# HFS_4011s_Rev_0.net
KiCad netlist of a schematic drawn in EAGLE
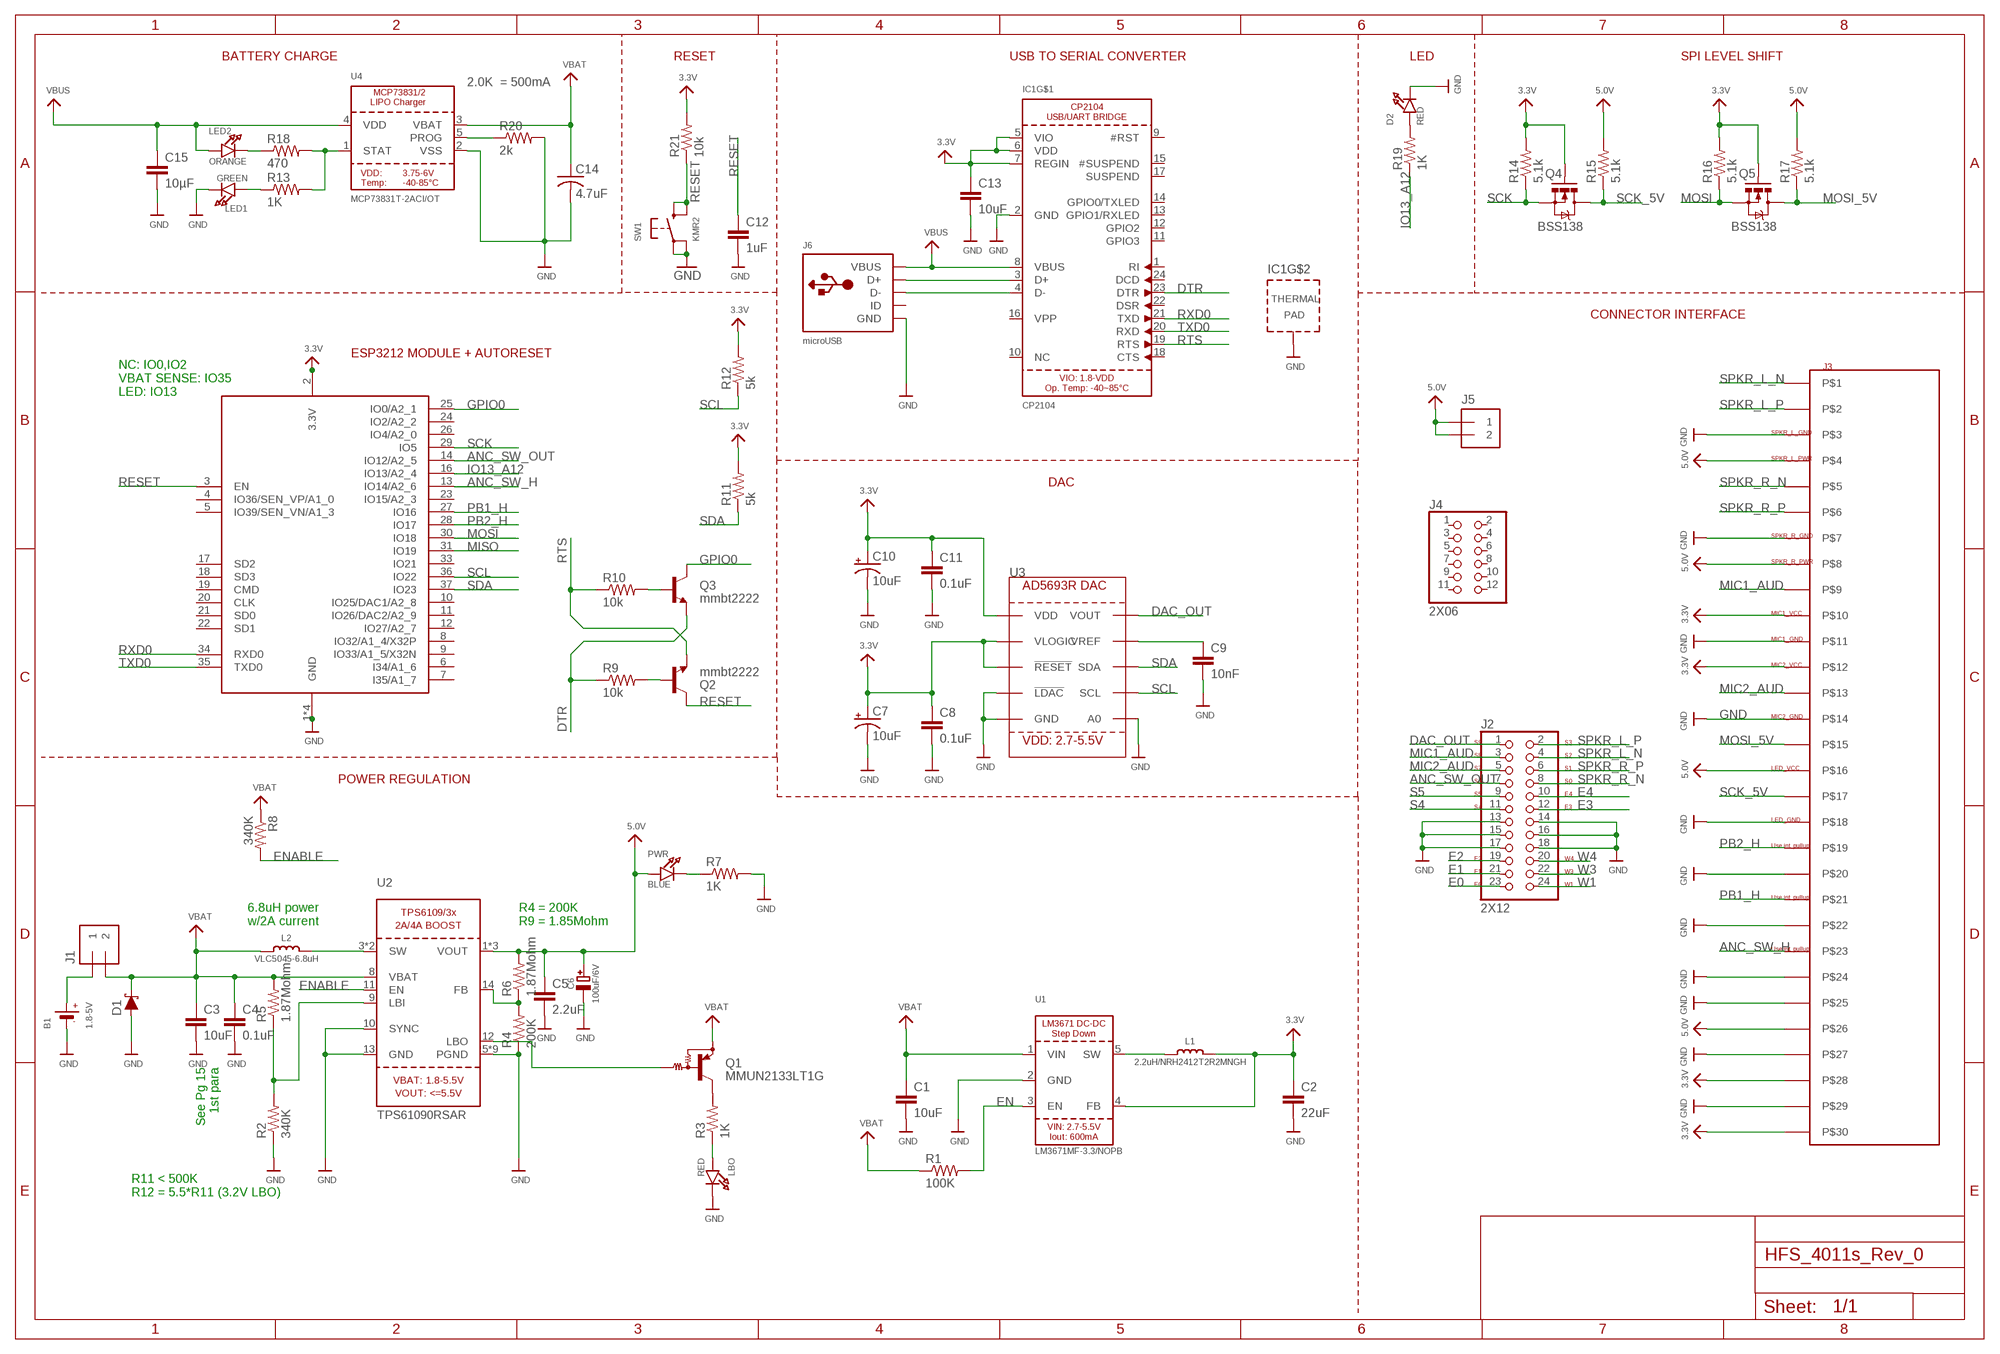
[diagram p0: schematic, sheet 1]

(export (version "E")
  (design (tool "Eeschema 10.0.6"))
  (components
    (comp (ref "B1")
      (value "1.8-5V")
      (footprint "eagle-import:JSTPH2")
      (libsource (lib "eagle-import") (part "BATTERY"))
    )
    (comp (ref "C1")
      (value "10uF")
      (footprint "eagle-import:C0603")
      (libsource (lib "eagle-import") (part "C-EUC0603"))
    )
    (comp (ref "C2")
      (value "22uF")
      (footprint "eagle-import:C0603")
      (libsource (lib "eagle-import") (part "C-EUC0603"))
    )
    (comp (ref "C3")
      (value "10uF")
      (footprint "eagle-import:C0603")
      (libsource (lib "eagle-import") (part "C-EUC0603"))
    )
    (comp (ref "C4")
      (value "0.1uF")
      (footprint "eagle-import:C0603")
      (libsource (lib "eagle-import") (part "C-EUC0603"))
    )
    (comp (ref "C5")
      (value "2.2uF")
      (footprint "eagle-import:C0603")
      (libsource (lib "eagle-import") (part "C-EUC0603"))
    )
    (comp (ref "C6")
      (value "100uF/6V")
      (footprint "eagle-import:EIA3528-21_B-R")
      (libsource (lib "eagle-import") (part "CAP_TANTALUMB/3528_REFLOW"))
    )
    (comp (ref "C7")
      (value "10uF")
      (footprint "eagle-import:EIA3216")
      (libsource (lib "eagle-import") (part "10UF-TANT"))
    )
    (comp (ref "C8")
      (value "0.1uF")
      (footprint "eagle-import:C0603")
      (libsource (lib "eagle-import") (part "C-EUC0603"))
    )
    (comp (ref "C9")
      (value "10nF")
      (footprint "eagle-import:C0603")
      (libsource (lib "eagle-import") (part "C-EUC0603"))
    )
    (comp (ref "C10")
      (value "10uF")
      (footprint "eagle-import:EIA3216")
      (libsource (lib "eagle-import") (part "10UF-TANT"))
    )
    (comp (ref "C11")
      (value "0.1uF")
      (footprint "eagle-import:C0603")
      (libsource (lib "eagle-import") (part "C-EUC0603"))
    )
    (comp (ref "C12")
      (value "1uF")
      (footprint "eagle-import:C0603")
      (libsource (lib "eagle-import") (part "C-EUC0603"))
    )
    (comp (ref "C13")
      (value "10uF")
      (footprint "eagle-import:C0603")
      (libsource (lib "eagle-import") (part "C-EUC0603"))
    )
    (comp (ref "C14")
      (value "4.7uF")
      (footprint "eagle-import:C1206")
      (libsource (lib "eagle-import") (part "C-USC1206"))
    )
    (comp (ref "C15")
      (value "10µF")
      (footprint "eagle-import:C0603")
      (libsource (lib "eagle-import") (part "C-EUC0603"))
    )
    (comp (ref "D1")
      (value "SMAJ5.0CALFDKR-ND")
      (footprint "eagle-import:DO-214AC")
      (libsource (lib "eagle-import") (part "SMAJ5.0CALFDKR-ND"))
    )
    (comp (ref "D2")
      (value "RED")
      (footprint "eagle-import:CHIPLED_0805_NOOUTLINE")
      (libsource (lib "eagle-import") (part "LED0805_NOOUTLINE"))
    )
    (comp (ref "IC1")
      (value "CP2104")
      (footprint "eagle-import:QFN24_4MM_SMSC")
      (libsource (lib "eagle-import") (part "CP2104"))
    )
    (comp (ref "J1")
      (value "1X02")
      (footprint "eagle-import:1X02")
      (libsource (lib "eagle-import") (part "1X02"))
    )
    (comp (ref "J2")
      (value "2X12")
      (footprint "eagle-import:2X12")
      (libsource (lib "eagle-import") (part "2X12"))
    )
    (comp (ref "J3")
      (value "MOLEX_IGRID_15X2CONNECTOR")
      (footprint "eagle-import:MOLEX_IGRID15X2CONNECTOR")
      (libsource (lib "eagle-import") (part "MOLEX_IGRID_15X2CONNECTOR"))
    )
    (comp (ref "J4")
      (value "2X06")
      (footprint "eagle-import:2X06")
      (libsource (lib "eagle-import") (part "2X06"))
    )
    (comp (ref "J5")
      (value "1X02")
      (footprint "eagle-import:1X02")
      (libsource (lib "eagle-import") (part "1X02"))
    )
    (comp (ref "J6")
      (value "microUSB")
      (footprint "eagle-import:4UCONN_20329")
      (libsource (lib "eagle-import") (part "USBMICRO_20329"))
    )
    (comp (ref "L1")
      (value "2.2uH/NRH2412T2R2MNGH")
      (footprint "eagle-import:INDUCTOR_TAIYOYUDEN_NRH2412T")
      (libsource (lib "eagle-import") (part "INDUCTORNRH2412T"))
    )
    (comp (ref "L2")
      (value "VLC5045-6.8uH")
      (footprint "eagle-import:INDUCTOR_5X5MM_TDK_VLC5045")
      (libsource (lib "eagle-import") (part "INDUCTORTDK_VLC5045"))
    )
    (comp (ref "LBO")
      (value "RED")
      (footprint "eagle-import:CHIPLED_0805_NOOUTLINE")
      (libsource (lib "eagle-import") (part "LED0805_NOOUTLINE"))
    )
    (comp (ref "LED1")
      (value "GREEN")
      (footprint "eagle-import:CHIPLED_0805_NOOUTLINE")
      (libsource (lib "eagle-import") (part "LED0805_NOOUTLINE"))
    )
    (comp (ref "LED2")
      (value "ORANGE")
      (footprint "eagle-import:CHIPLED_0805_NOOUTLINE")
      (libsource (lib "eagle-import") (part "LED0805_NOOUTLINE"))
    )
    (comp (ref "PWR")
      (value "BLUE")
      (footprint "eagle-import:CHIPLED_0805_NOOUTLINE")
      (libsource (lib "eagle-import") (part "LED0805_NOOUTLINE"))
    )
    (comp (ref "Q1")
      (value "MMUN2133LT1G")
      (footprint "eagle-import:SC59-BEC")
      (libsource (lib "eagle-import") (part "-PNP_DRIVER-SC59-BECMUN2114T1"))
    )
    (comp (ref "Q2")
      (value "mmbt2222")
      (footprint "eagle-import:SOT23-3")
      (libsource (lib "eagle-import") (part "TRANSISTOR_NPNSOT23-3"))
    )
    (comp (ref "Q3")
      (value "mmbt2222")
      (footprint "eagle-import:SOT23-3")
      (libsource (lib "eagle-import") (part "TRANSISTOR_NPNSOT23-3"))
    )
    (comp (ref "Q4")
      (value "BSS138")
      (footprint "eagle-import:SOT23-3")
      (libsource (lib "eagle-import") (part "MOSFET-NCHANNELSMD"))
    )
    (comp (ref "Q5")
      (value "BSS138")
      (footprint "eagle-import:SOT23-3")
      (libsource (lib "eagle-import") (part "MOSFET-NCHANNELSMD"))
    )
    (comp (ref "R1")
      (value "100K")
      (footprint "eagle-import:R0603")
      (libsource (lib "eagle-import") (part "R-US_R0603"))
    )
    (comp (ref "R2")
      (value "340K")
      (footprint "eagle-import:R0603")
      (libsource (lib "eagle-import") (part "R-US_R0603"))
    )
    (comp (ref "R3")
      (value "1K")
      (footprint "eagle-import:R0603")
      (libsource (lib "eagle-import") (part "R-US_R0603"))
    )
    (comp (ref "R4")
      (value "200K")
      (footprint "eagle-import:R0603")
      (libsource (lib "eagle-import") (part "R-US_R0603"))
    )
    (comp (ref "R5")
      (value "1.87Mohm")
      (footprint "eagle-import:R0603")
      (libsource (lib "eagle-import") (part "R-US_R0603"))
    )
    (comp (ref "R6")
      (value "1.87Mohm")
      (footprint "eagle-import:R0603")
      (libsource (lib "eagle-import") (part "R-US_R0603"))
    )
    (comp (ref "R7")
      (value "1K")
      (footprint "eagle-import:R0603")
      (libsource (lib "eagle-import") (part "R-US_R0603"))
    )
    (comp (ref "R8")
      (value "340K")
      (footprint "eagle-import:R0603")
      (libsource (lib "eagle-import") (part "R-US_R0603"))
    )
    (comp (ref "R9")
      (value "10k")
      (footprint "eagle-import:R0603")
      (libsource (lib "eagle-import") (part "R-US_R0603"))
    )
    (comp (ref "R10")
      (value "10k")
      (footprint "eagle-import:R0603")
      (libsource (lib "eagle-import") (part "R-US_R0603"))
    )
    (comp (ref "R11")
      (value "5k")
      (footprint "eagle-import:R0603")
      (libsource (lib "eagle-import") (part "R-US_R0603"))
    )
    (comp (ref "R12")
      (value "5k")
      (footprint "eagle-import:R0603")
      (libsource (lib "eagle-import") (part "R-US_R0603"))
    )
    (comp (ref "R13")
      (value "1K")
      (footprint "eagle-import:R0603")
      (libsource (lib "eagle-import") (part "R-US_R0603"))
    )
    (comp (ref "R14")
      (value "5.1k")
      (footprint "eagle-import:R0603")
      (libsource (lib "eagle-import") (part "R-US_R0603"))
    )
    (comp (ref "R15")
      (value "5.1k")
      (footprint "eagle-import:R0603")
      (libsource (lib "eagle-import") (part "R-US_R0603"))
    )
    (comp (ref "R16")
      (value "5.1k")
      (footprint "eagle-import:R0603")
      (libsource (lib "eagle-import") (part "R-US_R0603"))
    )
    (comp (ref "R17")
      (value "5.1k")
      (footprint "eagle-import:R0603")
      (libsource (lib "eagle-import") (part "R-US_R0603"))
    )
    (comp (ref "R18")
      (value "470")
      (footprint "eagle-import:R0603")
      (libsource (lib "eagle-import") (part "R-US_R0603"))
    )
    (comp (ref "R19")
      (value "1K")
      (footprint "eagle-import:R0603")
      (libsource (lib "eagle-import") (part "R-US_R0603"))
    )
    (comp (ref "R20")
      (value "2k")
      (footprint "eagle-import:R0603")
      (libsource (lib "eagle-import") (part "R-US_R0603"))
    )
    (comp (ref "R21")
      (value "10k")
      (footprint "eagle-import:R0603")
      (libsource (lib "eagle-import") (part "R-US_R0603"))
    )
    (comp (ref "SW1")
      (value "KMR2")
      (footprint "eagle-import:BTN_KMR2_4.6X2.8")
      (libsource (lib "eagle-import") (part "SWITCH_TACT_SMT4.6X2.8"))
    )
    (comp (ref "U1")
      (value "LM3671MF-3.3/NOPB")
      (footprint "eagle-import:SOT23-5")
      (libsource (lib "eagle-import") (part "VREG_LM3671"))
    )
    (comp (ref "U2")
      (value "TPS61090RSAR")
      (footprint "eagle-import:PVQFN-16")
      (libsource (lib "eagle-import") (part "VREG_TPS6103X"))
    )
    (comp (ref "U3")
      (value "AD5693R")
      (footprint "eagle-import:MSOP10")
      (libsource (lib "eagle-import") (part "AD5693R"))
    )
    (comp (ref "U4")
      (value "MCP73831T-2ACI/OT")
      (footprint "eagle-import:SOT23-5")
      (libsource (lib "eagle-import") (part "MCP73831/2"))
    )
    (comp (ref "X1")
      (value "ESP32_WROOM32_SKINNY")
      (footprint "eagle-import:WROOM32_SKINNY")
      (libsource (lib "eagle-import") (part "ESP32_WROOM32_SKINNY"))
    )
  )
  (nets
    (net (code "1") (name "/ANC_SW_H") (class "Default")
      (node (ref "J3") (pin "P$23") (pinfunction "P$23_P$23") (pintype "bidirectional"))
      (node (ref "X1") (pin "13") (pinfunction "IO14/A2_6_13") (pintype "bidirectional"))
    )
    (net (code "2") (name "/ANC_SW_OUT") (class "Default")
      (node (ref "J2") (pin "7") (pinfunction "7_7") (pintype "passive"))
      (node (ref "X1") (pin "14") (pinfunction "IO12/A2_5_14") (pintype "bidirectional"))
    )
    (net (code "3") (name "/DAC_OUT") (class "Default")
      (node (ref "J2") (pin "1") (pinfunction "1_1") (pintype "passive"))
      (node (ref "U3") (pin "10") (pinfunction "VOUT_10") (pintype "passive"))
    )
    (net (code "4") (name "/DTR") (class "Default")
      (node (ref "IC1") (pin "23") (pinfunction "DTR_23") (pintype "output"))
      (node (ref "Q3") (pin "2") (pinfunction "E_2") (pintype "passive"))
      (node (ref "R9") (pin "1") (pinfunction "1_1") (pintype "passive"))
    )
    (net (code "5") (name "/E0") (class "Default")
      (node (ref "J2") (pin "23") (pinfunction "23_23") (pintype "passive"))
    )
    (net (code "6") (name "/E1") (class "Default")
      (node (ref "J2") (pin "21") (pinfunction "21_21") (pintype "passive"))
    )
    (net (code "7") (name "/E2") (class "Default")
      (node (ref "J2") (pin "19") (pinfunction "19_19") (pintype "passive"))
    )
    (net (code "8") (name "/E3") (class "Default")
      (node (ref "J2") (pin "12") (pinfunction "12_12") (pintype "passive"))
    )
    (net (code "9") (name "/E4") (class "Default")
      (node (ref "J2") (pin "10") (pinfunction "10_10") (pintype "passive"))
    )
    (net (code "10") (name "/EN") (class "Default")
      (node (ref "R1") (pin "2") (pinfunction "2_2") (pintype "passive"))
      (node (ref "U1") (pin "3") (pinfunction "EN_3") (pintype "input"))
    )
    (net (code "11") (name "/ENABLE") (class "Default")
      (node (ref "R8") (pin "2") (pinfunction "2_2") (pintype "passive"))
      (node (ref "U2") (pin "11") (pinfunction "EN_11") (pintype "input"))
    )
    (net (code "12") (name "/GPIO0") (class "Default")
      (node (ref "Q3") (pin "3") (pinfunction "C_3") (pintype "passive"))
      (node (ref "X1") (pin "25") (pinfunction "IO0/A2_1_25") (pintype "bidirectional"))
    )
    (net (code "13") (name "/IO13_A12") (class "Default")
      (node (ref "R19") (pin "1") (pinfunction "1_1") (pintype "passive"))
      (node (ref "X1") (pin "16") (pinfunction "IO13/A2_4_16") (pintype "bidirectional"))
    )
    (net (code "14") (name "/MIC1_AUD") (class "Default")
      (node (ref "J2") (pin "3") (pinfunction "3_3") (pintype "passive"))
      (node (ref "J3") (pin "P$9") (pinfunction "P$9_P$9") (pintype "bidirectional"))
    )
    (net (code "15") (name "/MIC2_AUD") (class "Default")
      (node (ref "J2") (pin "5") (pinfunction "5_5") (pintype "passive"))
      (node (ref "J3") (pin "P$13") (pinfunction "P$13_P$13") (pintype "bidirectional"))
    )
    (net (code "16") (name "/MISO") (class "Default")
      (node (ref "X1") (pin "31") (pinfunction "IO19_31") (pintype "bidirectional"))
    )
    (net (code "17") (name "/MOSI") (class "Default")
      (node (ref "Q5") (pin "2") (pinfunction "S_2") (pintype "passive"))
      (node (ref "R16") (pin "1") (pinfunction "1_1") (pintype "passive"))
      (node (ref "X1") (pin "30") (pinfunction "IO18_30") (pintype "bidirectional"))
    )
    (net (code "18") (name "/MOSI_5V") (class "Default")
      (node (ref "J3") (pin "P$15") (pinfunction "P$15_P$15") (pintype "bidirectional"))
      (node (ref "Q5") (pin "3") (pinfunction "D_3") (pintype "passive"))
      (node (ref "R17") (pin "1") (pinfunction "1_1") (pintype "passive"))
    )
    (net (code "19") (name "/PB1_H") (class "Default")
      (node (ref "J3") (pin "P$21") (pinfunction "P$21_P$21") (pintype "bidirectional"))
      (node (ref "X1") (pin "27") (pinfunction "IO16_27") (pintype "bidirectional"))
    )
    (net (code "20") (name "/PB2_H") (class "Default")
      (node (ref "J3") (pin "P$19") (pinfunction "P$19_P$19") (pintype "bidirectional"))
      (node (ref "X1") (pin "28") (pinfunction "IO17_28") (pintype "bidirectional"))
    )
    (net (code "21") (name "/RESET") (class "Default")
      (node (ref "C12") (pin "1") (pinfunction "1_1") (pintype "passive"))
      (node (ref "Q2") (pin "3") (pinfunction "C_3") (pintype "passive"))
      (node (ref "R21") (pin "1") (pinfunction "1_1") (pintype "passive"))
      (node (ref "SW1") (pin "B") (pinfunction "S_B") (pintype "passive"))
      (node (ref "SW1") (pin "B'") (pinfunction "S1_B'") (pintype "passive"))
      (node (ref "X1") (pin "3") (pinfunction "EN_3") (pintype "input"))
    )
    (net (code "22") (name "/RTS") (class "Default")
      (node (ref "IC1") (pin "19") (pinfunction "RTS_19") (pintype "output"))
      (node (ref "Q2") (pin "2") (pinfunction "E_2") (pintype "passive"))
      (node (ref "R10") (pin "1") (pinfunction "1_1") (pintype "passive"))
    )
    (net (code "23") (name "/RXD0") (class "Default")
      (node (ref "IC1") (pin "21") (pinfunction "TXD_21") (pintype "output"))
      (node (ref "X1") (pin "34") (pinfunction "RXD0_34") (pintype "input"))
    )
    (net (code "24") (name "/S4") (class "Default")
      (node (ref "J2") (pin "11") (pinfunction "11_11") (pintype "passive"))
    )
    (net (code "25") (name "/S5") (class "Default")
      (node (ref "J2") (pin "9") (pinfunction "9_9") (pintype "passive"))
    )
    (net (code "26") (name "/SCK") (class "Default")
      (node (ref "Q4") (pin "2") (pinfunction "S_2") (pintype "passive"))
      (node (ref "R14") (pin "1") (pinfunction "1_1") (pintype "passive"))
      (node (ref "X1") (pin "29") (pinfunction "IO5_29") (pintype "bidirectional"))
    )
    (net (code "27") (name "/SCK_5V") (class "Default")
      (node (ref "J3") (pin "P$17") (pinfunction "P$17_P$17") (pintype "bidirectional"))
      (node (ref "Q4") (pin "3") (pinfunction "D_3") (pintype "passive"))
      (node (ref "R15") (pin "1") (pinfunction "1_1") (pintype "passive"))
    )
    (net (code "28") (name "/SCL") (class "Default")
      (node (ref "R12") (pin "1") (pinfunction "1_1") (pintype "passive"))
      (node (ref "U3") (pin "7") (pinfunction "SCL_7") (pintype "passive"))
      (node (ref "X1") (pin "36") (pinfunction "IO22_36") (pintype "bidirectional"))
    )
    (net (code "29") (name "/SDA") (class "Default")
      (node (ref "R11") (pin "1") (pinfunction "1_1") (pintype "passive"))
      (node (ref "U3") (pin "8") (pinfunction "SDA_8") (pintype "passive"))
      (node (ref "X1") (pin "37") (pinfunction "IO23_37") (pintype "bidirectional"))
    )
    (net (code "30") (name "/SPKR_L_N") (class "Default")
      (node (ref "J2") (pin "4") (pinfunction "4_4") (pintype "passive"))
      (node (ref "J3") (pin "P$1") (pinfunction "P$1_P$1") (pintype "bidirectional"))
    )
    (net (code "31") (name "/SPKR_L_P") (class "Default")
      (node (ref "J2") (pin "2") (pinfunction "2_2") (pintype "passive"))
      (node (ref "J3") (pin "P$2") (pinfunction "P$2_P$2") (pintype "bidirectional"))
    )
    (net (code "32") (name "/SPKR_R_N") (class "Default")
      (node (ref "J2") (pin "8") (pinfunction "8_8") (pintype "passive"))
      (node (ref "J3") (pin "P$5") (pinfunction "P$5_P$5") (pintype "bidirectional"))
    )
    (net (code "33") (name "/SPKR_R_P") (class "Default")
      (node (ref "J2") (pin "6") (pinfunction "6_6") (pintype "passive"))
      (node (ref "J3") (pin "P$6") (pinfunction "P$6_P$6") (pintype "bidirectional"))
    )
    (net (code "34") (name "/TXD0") (class "Default")
      (node (ref "IC1") (pin "20") (pinfunction "RXD_20") (pintype "input"))
      (node (ref "X1") (pin "35") (pinfunction "TXD0_35") (pintype "output"))
    )
    (net (code "35") (name "/W1") (class "Default")
      (node (ref "J2") (pin "24") (pinfunction "24_24") (pintype "passive"))
    )
    (net (code "36") (name "/W3") (class "Default")
      (node (ref "J2") (pin "22") (pinfunction "22_22") (pintype "passive"))
    )
    (net (code "37") (name "/W4") (class "Default")
      (node (ref "J2") (pin "20") (pinfunction "20_20") (pintype "passive"))
    )
    (net (code "38") (name "3.3V") (class "Default")
      (node (ref "C10") (pin "A") (pinfunction "+_A") (pintype "passive"))
      (node (ref "C11") (pin "1") (pinfunction "1_1") (pintype "passive"))
      (node (ref "C13") (pin "1") (pinfunction "1_1") (pintype "passive"))
      (node (ref "C2") (pin "1") (pinfunction "1_1") (pintype "passive"))
      (node (ref "C7") (pin "A") (pinfunction "+_A") (pintype "passive"))
      (node (ref "C8") (pin "1") (pinfunction "1_1") (pintype "passive"))
      (node (ref "IC1") (pin "5") (pinfunction "VIO_5") (pintype "power_in"))
      (node (ref "IC1") (pin "6") (pinfunction "VDD_6") (pintype "power_in"))
      (node (ref "IC1") (pin "7") (pinfunction "REGIN_7") (pintype "power_in"))
      (node (ref "J3") (pin "P$10") (pinfunction "P$10_P$10") (pintype "bidirectional"))
      (node (ref "J3") (pin "P$12") (pinfunction "P$12_P$12") (pintype "bidirectional"))
      (node (ref "J3") (pin "P$28") (pinfunction "P$28_P$28") (pintype "bidirectional"))
      (node (ref "J3") (pin "P$30") (pinfunction "P$30_P$30") (pintype "bidirectional"))
      (node (ref "L1") (pin "2") (pinfunction "2_2") (pintype "passive"))
      (node (ref "Q4") (pin "1") (pinfunction "G_1") (pintype "passive"))
      (node (ref "Q5") (pin "1") (pinfunction "G_1") (pintype "passive"))
      (node (ref "R11") (pin "2") (pinfunction "2_2") (pintype "passive"))
      (node (ref "R12") (pin "2") (pinfunction "2_2") (pintype "passive"))
      (node (ref "R14") (pin "2") (pinfunction "2_2") (pintype "passive"))
      (node (ref "R16") (pin "2") (pinfunction "2_2") (pintype "passive"))
      (node (ref "R21") (pin "2") (pinfunction "2_2") (pintype "passive"))
      (node (ref "U1") (pin "4") (pinfunction "FB_4") (pintype "power_in"))
      (node (ref "U3") (pin "1") (pinfunction "VDD_1") (pintype "passive"))
      (node (ref "U3") (pin "2") (pinfunction "VLOGIC_2") (pintype "passive"))
      (node (ref "U3") (pin "3") (pinfunction "~{RESET}_3") (pintype "passive"))
      (node (ref "X1") (pin "2") (pinfunction "3.3V_2") (pintype "passive"))
    )
    (net (code "39") (name "5.0V") (class "Default")
      (node (ref "C5") (pin "1") (pinfunction "1_1") (pintype "passive"))
      (node (ref "C6") (pin "+") (pinfunction "+_+") (pintype "passive"))
      (node (ref "J3") (pin "P$16") (pinfunction "P$16_P$16") (pintype "bidirectional"))
      (node (ref "J3") (pin "P$26") (pinfunction "P$26_P$26") (pintype "bidirectional"))
      (node (ref "J3") (pin "P$4") (pinfunction "P$4_P$4") (pintype "bidirectional"))
      (node (ref "J3") (pin "P$8") (pinfunction "P$8_P$8") (pintype "bidirectional"))
      (node (ref "J5") (pin "1") (pinfunction "1_1") (pintype "passive"))
      (node (ref "J5") (pin "2") (pinfunction "2_2") (pintype "passive"))
      (node (ref "PWR") (pin "A") (pinfunction "A_A") (pintype "passive"))
      (node (ref "R15") (pin "2") (pinfunction "2_2") (pintype "passive"))
      (node (ref "R17") (pin "2") (pinfunction "2_2") (pintype "passive"))
      (node (ref "R6") (pin "2") (pinfunction "2_2") (pintype "passive"))
      (node (ref "U2") (pin "1") (pinfunction "VOUT_1") (pintype "power_in"))
      (node (ref "U2") (pin "15") (pinfunction "VOUT_15") (pintype "power_in"))
      (node (ref "U2") (pin "16") (pinfunction "VOUT_16") (pintype "power_in"))
    )
    (net (code "40") (name "GND") (class "Default")
      (node (ref "B1") (pin "1") (pinfunction "-_1") (pintype "passive"))
      (node (ref "C1") (pin "2") (pinfunction "2_2") (pintype "passive"))
      (node (ref "C10") (pin "C") (pinfunction "-_C") (pintype "passive"))
      (node (ref "C11") (pin "2") (pinfunction "2_2") (pintype "passive"))
      (node (ref "C12") (pin "2") (pinfunction "2_2") (pintype "passive"))
      (node (ref "C13") (pin "2") (pinfunction "2_2") (pintype "passive"))
      (node (ref "C14") (pin "2") (pinfunction "2_2") (pintype "passive"))
      (node (ref "C15") (pin "2") (pinfunction "2_2") (pintype "passive"))
      (node (ref "C2") (pin "2") (pinfunction "2_2") (pintype "passive"))
      (node (ref "C3") (pin "2") (pinfunction "2_2") (pintype "passive"))
      (node (ref "C4") (pin "2") (pinfunction "2_2") (pintype "passive"))
      (node (ref "C5") (pin "2") (pinfunction "2_2") (pintype "passive"))
      (node (ref "C6") (pin "-") (pinfunction "-_-") (pintype "passive"))
      (node (ref "C7") (pin "C") (pinfunction "-_C") (pintype "passive"))
      (node (ref "C8") (pin "2") (pinfunction "2_2") (pintype "passive"))
      (node (ref "C9") (pin "2") (pinfunction "2_2") (pintype "passive"))
      (node (ref "D1") (pin "A") (pinfunction "A_A") (pintype "passive"))
      (node (ref "D2") (pin "C") (pinfunction "C_C") (pintype "passive"))
      (node (ref "IC1") (pin "2") (pinfunction "GND_2") (pintype "power_in"))
      (node (ref "IC1") (pin "THERM") (pinfunction "TP_THERM") (pintype "power_in"))
      (node (ref "J2") (pin "13") (pinfunction "13_13") (pintype "passive"))
      (node (ref "J2") (pin "14") (pinfunction "14_14") (pintype "passive"))
      (node (ref "J2") (pin "15") (pinfunction "15_15") (pintype "passive"))
      (node (ref "J2") (pin "16") (pinfunction "16_16") (pintype "passive"))
      (node (ref "J2") (pin "17") (pinfunction "17_17") (pintype "passive"))
      (node (ref "J2") (pin "18") (pinfunction "18_18") (pintype "passive"))
      (node (ref "J3") (pin "P$11") (pinfunction "P$11_P$11") (pintype "bidirectional"))
      (node (ref "J3") (pin "P$14") (pinfunction "P$14_P$14") (pintype "bidirectional"))
      (node (ref "J3") (pin "P$18") (pinfunction "P$18_P$18") (pintype "bidirectional"))
      (node (ref "J3") (pin "P$20") (pinfunction "P$20_P$20") (pintype "bidirectional"))
      (node (ref "J3") (pin "P$22") (pinfunction "P$22_P$22") (pintype "bidirectional"))
      (node (ref "J3") (pin "P$24") (pinfunction "P$24_P$24") (pintype "bidirectional"))
      (node (ref "J3") (pin "P$25") (pinfunction "P$25_P$25") (pintype "bidirectional"))
      (node (ref "J3") (pin "P$27") (pinfunction "P$27_P$27") (pintype "bidirectional"))
      (node (ref "J3") (pin "P$29") (pinfunction "P$29_P$29") (pintype "bidirectional"))
      (node (ref "J3") (pin "P$3") (pinfunction "P$3_P$3") (pintype "bidirectional"))
      (node (ref "J3") (pin "P$7") (pinfunction "P$7_P$7") (pintype "bidirectional"))
      (node (ref "J6") (pin "BASE@1") (pinfunction "GND_BASE@1") (pintype "power_in"))
      (node (ref "J6") (pin "BASE@2") (pinfunction "GND_BASE@2") (pintype "power_in"))
      (node (ref "J6") (pin "GND") (pinfunction "GND_GND") (pintype "power_in"))
      (node (ref "J6") (pin "SPRT@1") (pinfunction "GND_SPRT@1") (pintype "power_in"))
      (node (ref "J6") (pin "SPRT@2") (pinfunction "GND_SPRT@2") (pintype "power_in"))
      (node (ref "J6") (pin "SPRT@3") (pinfunction "GND_SPRT@3") (pintype "power_in"))
      (node (ref "J6") (pin "SPRT@4") (pinfunction "GND_SPRT@4") (pintype "power_in"))
      (node (ref "LBO") (pin "C") (pinfunction "C_C") (pintype "passive"))
      (node (ref "LED1") (pin "C") (pinfunction "C_C") (pintype "passive"))
      (node (ref "R2") (pin "1") (pinfunction "1_1") (pintype "passive"))
      (node (ref "R20") (pin "2") (pinfunction "2_2") (pintype "passive"))
      (node (ref "R4") (pin "1") (pinfunction "1_1") (pintype "passive"))
      (node (ref "R7") (pin "2") (pinfunction "2_2") (pintype "passive"))
      (node (ref "SW1") (pin "A") (pinfunction "P_A") (pintype "passive"))
      (node (ref "SW1") (pin "A'") (pinfunction "P1_A'") (pintype "passive"))
      (node (ref "U1") (pin "2") (pinfunction "GND_2") (pintype "power_in"))
      (node (ref "U2") (pin "10") (pinfunction "SYNC_10") (pintype "input"))
      (node (ref "U2") (pin "13") (pinfunction "GND_13") (pintype "power_in"))
      (node (ref "U2") (pin "5") (pinfunction "PGND_5") (pintype "power_in"))
      (node (ref "U2") (pin "6") (pinfunction "PGND_6") (pintype "power_in"))
      (node (ref "U2") (pin "7") (pinfunction "PGND_7") (pintype "power_in"))
      (node (ref "U2") (pin "P$18") (pinfunction "PGND_P$18") (pintype "power_in"))
      (node (ref "U2") (pin "P$19") (pinfunction "PGND_P$19") (pintype "power_in"))
      (node (ref "U2") (pin "P$20") (pinfunction "PGND_P$20") (pintype "power_in"))
      (node (ref "U2") (pin "P$21") (pinfunction "PGND_P$21") (pintype "power_in"))
      (node (ref "U2") (pin "P$22") (pinfunction "PGND_P$22") (pintype "power_in"))
      (node (ref "U2") (pin "THERMAL") (pinfunction "PGND_THERMAL") (pintype "power_in"))
      (node (ref "U3") (pin "4") (pinfunction "~{LDAC}_4") (pintype "passive"))
      (node (ref "U3") (pin "5") (pinfunction "GND_5") (pintype "passive"))
      (node (ref "U3") (pin "6") (pinfunction "A0_6") (pintype "passive"))
      (node (ref "U4") (pin "2") (pinfunction "VSS_2") (pintype "power_in"))
      (node (ref "X1") (pin "1") (pinfunction "GND_1") (pintype "passive"))
      (node (ref "X1") (pin "15") (pinfunction "GND_15") (pintype "passive"))
      (node (ref "X1") (pin "38") (pinfunction "GND_38") (pintype "passive"))
      (node (ref "X1") (pin "P$1") (pinfunction "GND_P$1") (pintype "passive"))
    )
    (net (code "41") (name "Net-(B1-+)") (class "Default")
      (node (ref "B1") (pin "2") (pinfunction "+_2") (pintype "passive"))
      (node (ref "J1") (pin "1") (pinfunction "1_1") (pintype "passive"))
    )
    (net (code "42") (name "Net-(D2-PadA)") (class "Default")
      (node (ref "D2") (pin "A") (pinfunction "A_A") (pintype "passive"))
      (node (ref "R19") (pin "2") (pinfunction "2_2") (pintype "passive"))
    )
    (net (code "43") (name "Net-(IC1A-D+)") (class "Default")
      (node (ref "IC1") (pin "3") (pinfunction "D+_3") (pintype "bidirectional"))
      (node (ref "J6") (pin "D+") (pinfunction "D+_D+") (pintype "bidirectional"))
    )
    (net (code "44") (name "Net-(IC1A-D-)") (class "Default")
      (node (ref "IC1") (pin "4") (pinfunction "D-_4") (pintype "bidirectional"))
      (node (ref "J6") (pin "D-") (pinfunction "D-_D-") (pintype "bidirectional"))
    )
    (net (code "45") (name "Net-(L2-2)") (class "Default")
      (node (ref "L2") (pin "P$2") (pinfunction "2_P$2") (pintype "passive"))
      (node (ref "U2") (pin "3") (pinfunction "SW_3") (pintype "input"))
      (node (ref "U2") (pin "4") (pinfunction "SW_4") (pintype "input"))
    )
    (net (code "46") (name "Net-(LBO-PadA)") (class "Default")
      (node (ref "LBO") (pin "A") (pinfunction "A_A") (pintype "passive"))
      (node (ref "R3") (pin "1") (pinfunction "1_1") (pintype "passive"))
    )
    (net (code "47") (name "Net-(LED1-PadA)") (class "Default")
      (node (ref "LED1") (pin "A") (pinfunction "A_A") (pintype "passive"))
      (node (ref "R13") (pin "1") (pinfunction "1_1") (pintype "passive"))
    )
    (net (code "48") (name "Net-(LED2-PadC)") (class "Default")
      (node (ref "LED2") (pin "C") (pinfunction "C_C") (pintype "passive"))
      (node (ref "R18") (pin "1") (pinfunction "1_1") (pintype "passive"))
    )
    (net (code "49") (name "Net-(PWR-PadC)") (class "Default")
      (node (ref "PWR") (pin "C") (pinfunction "C_C") (pintype "passive"))
      (node (ref "R7") (pin "1") (pinfunction "1_1") (pintype "passive"))
    )
    (net (code "50") (name "Net-(Q1-PadC)") (class "Default")
      (node (ref "Q1") (pin "C") (pinfunction "C_C") (pintype "passive"))
      (node (ref "R3") (pin "2") (pinfunction "2_2") (pintype "passive"))
    )
    (net (code "51") (name "Net-(Q2-B)") (class "Default")
      (node (ref "Q2") (pin "1") (pinfunction "B_1") (pintype "passive"))
      (node (ref "R9") (pin "2") (pinfunction "2_2") (pintype "passive"))
    )
    (net (code "52") (name "Net-(Q3-B)") (class "Default")
      (node (ref "Q3") (pin "1") (pinfunction "B_1") (pintype "passive"))
      (node (ref "R10") (pin "2") (pinfunction "2_2") (pintype "passive"))
    )
    (net (code "53") (name "Net-(U1-SW)") (class "Default")
      (node (ref "L1") (pin "1") (pinfunction "1_1") (pintype "passive"))
      (node (ref "U1") (pin "5") (pinfunction "SW_5") (pintype "output"))
    )
    (net (code "54") (name "Net-(U2-FB)") (class "Default")
      (node (ref "R4") (pin "2") (pinfunction "2_2") (pintype "passive"))
      (node (ref "R6") (pin "1") (pinfunction "1_1") (pintype "passive"))
      (node (ref "U2") (pin "14") (pinfunction "FB_14") (pintype "input"))
    )
    (net (code "55") (name "Net-(U2-LBI)") (class "Default")
      (node (ref "R2") (pin "2") (pinfunction "2_2") (pintype "passive"))
      (node (ref "R5") (pin "1") (pinfunction "1_1") (pintype "passive"))
      (node (ref "U2") (pin "9") (pinfunction "LBI_9") (pintype "input"))
    )
    (net (code "56") (name "Net-(U2-LBO)") (class "Default")
      (node (ref "Q1") (pin "B") (pinfunction "B_B") (pintype "passive"))
      (node (ref "U2") (pin "12") (pinfunction "LBO_12") (pintype "output"))
    )
    (net (code "57") (name "Net-(U3-VREF)") (class "Default")
      (node (ref "C9") (pin "1") (pinfunction "1_1") (pintype "passive"))
      (node (ref "U3") (pin "9") (pinfunction "VREF_9") (pintype "passive"))
    )
    (net (code "58") (name "Net-(U4-PROG)") (class "Default")
      (node (ref "R20") (pin "1") (pinfunction "1_1") (pintype "passive"))
      (node (ref "U4") (pin "5") (pinfunction "PROG_5") (pintype "input"))
    )
    (net (code "59") (name "Net-(U4-STAT)") (class "Default")
      (node (ref "R13") (pin "2") (pinfunction "2_2") (pintype "passive"))
      (node (ref "R18") (pin "2") (pinfunction "2_2") (pintype "passive"))
      (node (ref "U4") (pin "1") (pinfunction "STAT_1") (pintype "output"))
    )
    (net (code "60") (name "VBAT") (class "Default")
      (node (ref "C1") (pin "1") (pinfunction "1_1") (pintype "passive"))
      (node (ref "C14") (pin "1") (pinfunction "1_1") (pintype "passive"))
      (node (ref "C3") (pin "1") (pinfunction "1_1") (pintype "passive"))
      (node (ref "C4") (pin "1") (pinfunction "1_1") (pintype "passive"))
      (node (ref "D1") (pin "C") (pinfunction "C_C") (pintype "passive"))
      (node (ref "J1") (pin "2") (pinfunction "2_2") (pintype "passive"))
      (node (ref "L2") (pin "P$1") (pinfunction "1_P$1") (pintype "passive"))
      (node (ref "Q1") (pin "E") (pinfunction "E_E") (pintype "passive"))
      (node (ref "R1") (pin "1") (pinfunction "1_1") (pintype "passive"))
      (node (ref "R5") (pin "2") (pinfunction "2_2") (pintype "passive"))
      (node (ref "R8") (pin "1") (pinfunction "1_1") (pintype "passive"))
      (node (ref "U1") (pin "1") (pinfunction "VIN_1") (pintype "power_in"))
      (node (ref "U2") (pin "8") (pinfunction "VBAT_8") (pintype "input"))
      (node (ref "U4") (pin "3") (pinfunction "VBAT_3") (pintype "power_in"))
    )
    (net (code "61") (name "VBUS") (class "Default")
      (node (ref "C15") (pin "1") (pinfunction "1_1") (pintype "passive"))
      (node (ref "IC1") (pin "8") (pinfunction "VBUS_8") (pintype "power_in"))
      (node (ref "J6") (pin "VBUS") (pinfunction "VBUS_VBUS") (pintype "power_in"))
      (node (ref "LED2") (pin "A") (pinfunction "A_A") (pintype "passive"))
      (node (ref "U4") (pin "4") (pinfunction "VDD_4") (pintype "power_in"))
    )
    (net (code "62") (name "unconnected-(IC1A-#RST-Pad9)") (class "Default")
      (node (ref "IC1") (pin "9") (pinfunction "#RST_9") (pintype "bidirectional"))
    )
    (net (code "63") (name "unconnected-(IC1A-#SUSPEND-Pad15)") (class "Default")
      (node (ref "IC1") (pin "15") (pinfunction "#SUSPEND_15") (pintype "output"))
    )
    (net (code "64") (name "unconnected-(IC1A-CTS-Pad18)") (class "Default")
      (node (ref "IC1") (pin "18") (pinfunction "CTS_18") (pintype "input"))
    )
    (net (code "65") (name "unconnected-(IC1A-DCD-Pad24)") (class "Default")
      (node (ref "IC1") (pin "24") (pinfunction "DCD_24") (pintype "input"))
    )
    (net (code "66") (name "unconnected-(IC1A-DSR-Pad22)") (class "Default")
      (node (ref "IC1") (pin "22") (pinfunction "DSR_22") (pintype "input"))
    )
    (net (code "67") (name "unconnected-(IC1A-GPIO0{slash}TXLED-Pad14)") (class "Default")
      (node (ref "IC1") (pin "14") (pinfunction "GPIO0/TXLED_14") (pintype "bidirectional"))
    )
    (net (code "68") (name "unconnected-(IC1A-GPIO1{slash}RXLED-Pad13)") (class "Default")
      (node (ref "IC1") (pin "13") (pinfunction "GPIO1/RXLED_13") (pintype "bidirectional"))
    )
    (net (code "69") (name "unconnected-(IC1A-GPIO2-Pad12)") (class "Default")
      (node (ref "IC1") (pin "12") (pinfunction "GPIO2_12") (pintype "bidirectional"))
    )
    (net (code "70") (name "unconnected-(IC1A-GPIO3-Pad11)") (class "Default")
      (node (ref "IC1") (pin "11") (pinfunction "GPIO3_11") (pintype "bidirectional"))
    )
    (net (code "71") (name "unconnected-(IC1A-NC-Pad10)") (class "Default")
      (node (ref "IC1") (pin "10") (pinfunction "NC_10") (pintype "no_connect"))
    )
    (net (code "72") (name "unconnected-(IC1A-RI-Pad1)") (class "Default")
      (node (ref "IC1") (pin "1") (pinfunction "RI_1") (pintype "input"))
    )
    (net (code "73") (name "unconnected-(IC1A-SUSPEND-Pad17)") (class "Default")
      (node (ref "IC1") (pin "17") (pinfunction "SUSPEND_17") (pintype "output"))
    )
    (net (code "74") (name "unconnected-(IC1A-VPP-Pad16)") (class "Default")
      (node (ref "IC1") (pin "16") (pinfunction "VPP_16") (pintype "bidirectional"))
    )
    (net (code "75") (name "unconnected-(J4-Pad1)") (class "Default")
      (node (ref "J4") (pin "1") (pinfunction "1_1") (pintype "passive"))
    )
    (net (code "76") (name "unconnected-(J4-Pad2)") (class "Default")
      (node (ref "J4") (pin "2") (pinfunction "2_2") (pintype "passive"))
    )
    (net (code "77") (name "unconnected-(J4-Pad3)") (class "Default")
      (node (ref "J4") (pin "3") (pinfunction "3_3") (pintype "passive"))
    )
    (net (code "78") (name "unconnected-(J4-Pad4)") (class "Default")
      (node (ref "J4") (pin "4") (pinfunction "4_4") (pintype "passive"))
    )
    (net (code "79") (name "unconnected-(J4-Pad5)") (class "Default")
      (node (ref "J4") (pin "5") (pinfunction "5_5") (pintype "passive"))
    )
    (net (code "80") (name "unconnected-(J4-Pad6)") (class "Default")
      (node (ref "J4") (pin "6") (pinfunction "6_6") (pintype "passive"))
    )
    (net (code "81") (name "unconnected-(J4-Pad7)") (class "Default")
      (node (ref "J4") (pin "7") (pinfunction "7_7") (pintype "passive"))
    )
    (net (code "82") (name "unconnected-(J4-Pad8)") (class "Default")
      (node (ref "J4") (pin "8") (pinfunction "8_8") (pintype "passive"))
    )
    (net (code "83") (name "unconnected-(J4-Pad9)") (class "Default")
      (node (ref "J4") (pin "9") (pinfunction "9_9") (pintype "passive"))
    )
    (net (code "84") (name "unconnected-(J4-Pad10)") (class "Default")
      (node (ref "J4") (pin "10") (pinfunction "10_10") (pintype "passive"))
    )
    (net (code "85") (name "unconnected-(J4-Pad11)") (class "Default")
      (node (ref "J4") (pin "11") (pinfunction "11_11") (pintype "passive"))
    )
    (net (code "86") (name "unconnected-(J4-Pad12)") (class "Default")
      (node (ref "J4") (pin "12") (pinfunction "12_12") (pintype "passive"))
    )
    (net (code "87") (name "unconnected-(J6-PadID)") (class "Default")
      (node (ref "J6") (pin "ID") (pinfunction "ID_ID") (pintype "bidirectional"))
    )
    (net (code "88") (name "unconnected-(X1-CLK-Pad20)") (class "Default")
      (node (ref "X1") (pin "20") (pinfunction "CLK_20") (pintype "bidirectional"))
    )
    (net (code "89") (name "unconnected-(X1-CMD-Pad19)") (class "Default")
      (node (ref "X1") (pin "19") (pinfunction "CMD_19") (pintype "bidirectional"))
    )
    (net (code "90") (name "unconnected-(X1-I34{slash}A1_6-Pad6)") (class "Default")
      (node (ref "X1") (pin "6") (pinfunction "I34/A1_6_6") (pintype "bidirectional"))
    )
    (net (code "91") (name "unconnected-(X1-I35{slash}A1_7-Pad7)") (class "Default")
      (node (ref "X1") (pin "7") (pinfunction "I35/A1_7_7") (pintype "bidirectional"))
    )
    (net (code "92") (name "unconnected-(X1-IO2{slash}A2_2-Pad24)") (class "Default")
      (node (ref "X1") (pin "24") (pinfunction "IO2/A2_2_24") (pintype "bidirectional"))
    )
    (net (code "93") (name "unconnected-(X1-IO4{slash}A2_0-Pad26)") (class "Default")
      (node (ref "X1") (pin "26") (pinfunction "IO4/A2_0_26") (pintype "bidirectional"))
    )
    (net (code "94") (name "unconnected-(X1-IO15{slash}A2_3-Pad23)") (class "Default")
      (node (ref "X1") (pin "23") (pinfunction "IO15/A2_3_23") (pintype "bidirectional"))
    )
    (net (code "95") (name "unconnected-(X1-IO21-Pad33)") (class "Default")
      (node (ref "X1") (pin "33") (pinfunction "IO21_33") (pintype "bidirectional"))
    )
    (net (code "96") (name "unconnected-(X1-IO25{slash}DAC1{slash}A2_8-Pad10)") (class "Default")
      (node (ref "X1") (pin "10") (pinfunction "IO25/DAC1/A2_8_10") (pintype "bidirectional"))
    )
    (net (code "97") (name "unconnected-(X1-IO26{slash}DAC2{slash}A2_9-Pad11)") (class "Default")
      (node (ref "X1") (pin "11") (pinfunction "IO26/DAC2/A2_9_11") (pintype "bidirectional"))
    )
    (net (code "98") (name "unconnected-(X1-IO27{slash}A2_7-Pad12)") (class "Default")
      (node (ref "X1") (pin "12") (pinfunction "IO27/A2_7_12") (pintype "bidirectional"))
    )
    (net (code "99") (name "unconnected-(X1-IO32{slash}A1_4{slash}X32P-Pad8)") (class "Default")
      (node (ref "X1") (pin "8") (pinfunction "IO32/A1_4/X32P_8") (pintype "bidirectional"))
    )
    (net (code "100") (name "unconnected-(X1-IO33{slash}A1_5{slash}X32N-Pad9)") (class "Default")
      (node (ref "X1") (pin "9") (pinfunction "IO33/A1_5/X32N_9") (pintype "bidirectional"))
    )
    (net (code "101") (name "unconnected-(X1-IO36{slash}SEN_VP{slash}A1_0-Pad4)") (class "Default")
      (node (ref "X1") (pin "4") (pinfunction "IO36/SEN_VP/A1_0_4") (pintype "passive"))
    )
    (net (code "102") (name "unconnected-(X1-IO39{slash}SEN_VN{slash}A1_3-Pad5)") (class "Default")
      (node (ref "X1") (pin "5") (pinfunction "IO39/SEN_VN/A1_3_5") (pintype "passive"))
    )
    (net (code "103") (name "unconnected-(X1-SD0-Pad21)") (class "Default")
      (node (ref "X1") (pin "21") (pinfunction "SD0_21") (pintype "bidirectional"))
    )
    (net (code "104") (name "unconnected-(X1-SD1-Pad22)") (class "Default")
      (node (ref "X1") (pin "22") (pinfunction "SD1_22") (pintype "bidirectional"))
    )
    (net (code "105") (name "unconnected-(X1-SD2-Pad17)") (class "Default")
      (node (ref "X1") (pin "17") (pinfunction "SD2_17") (pintype "bidirectional"))
    )
    (net (code "106") (name "unconnected-(X1-SD3-Pad18)") (class "Default")
      (node (ref "X1") (pin "18") (pinfunction "SD3_18") (pintype "bidirectional"))
    )
  )
)
